# SparkFun_MicroMod_Function_Board_Blues_N.net
KiCad netlist of a schematic drawn in EAGLE
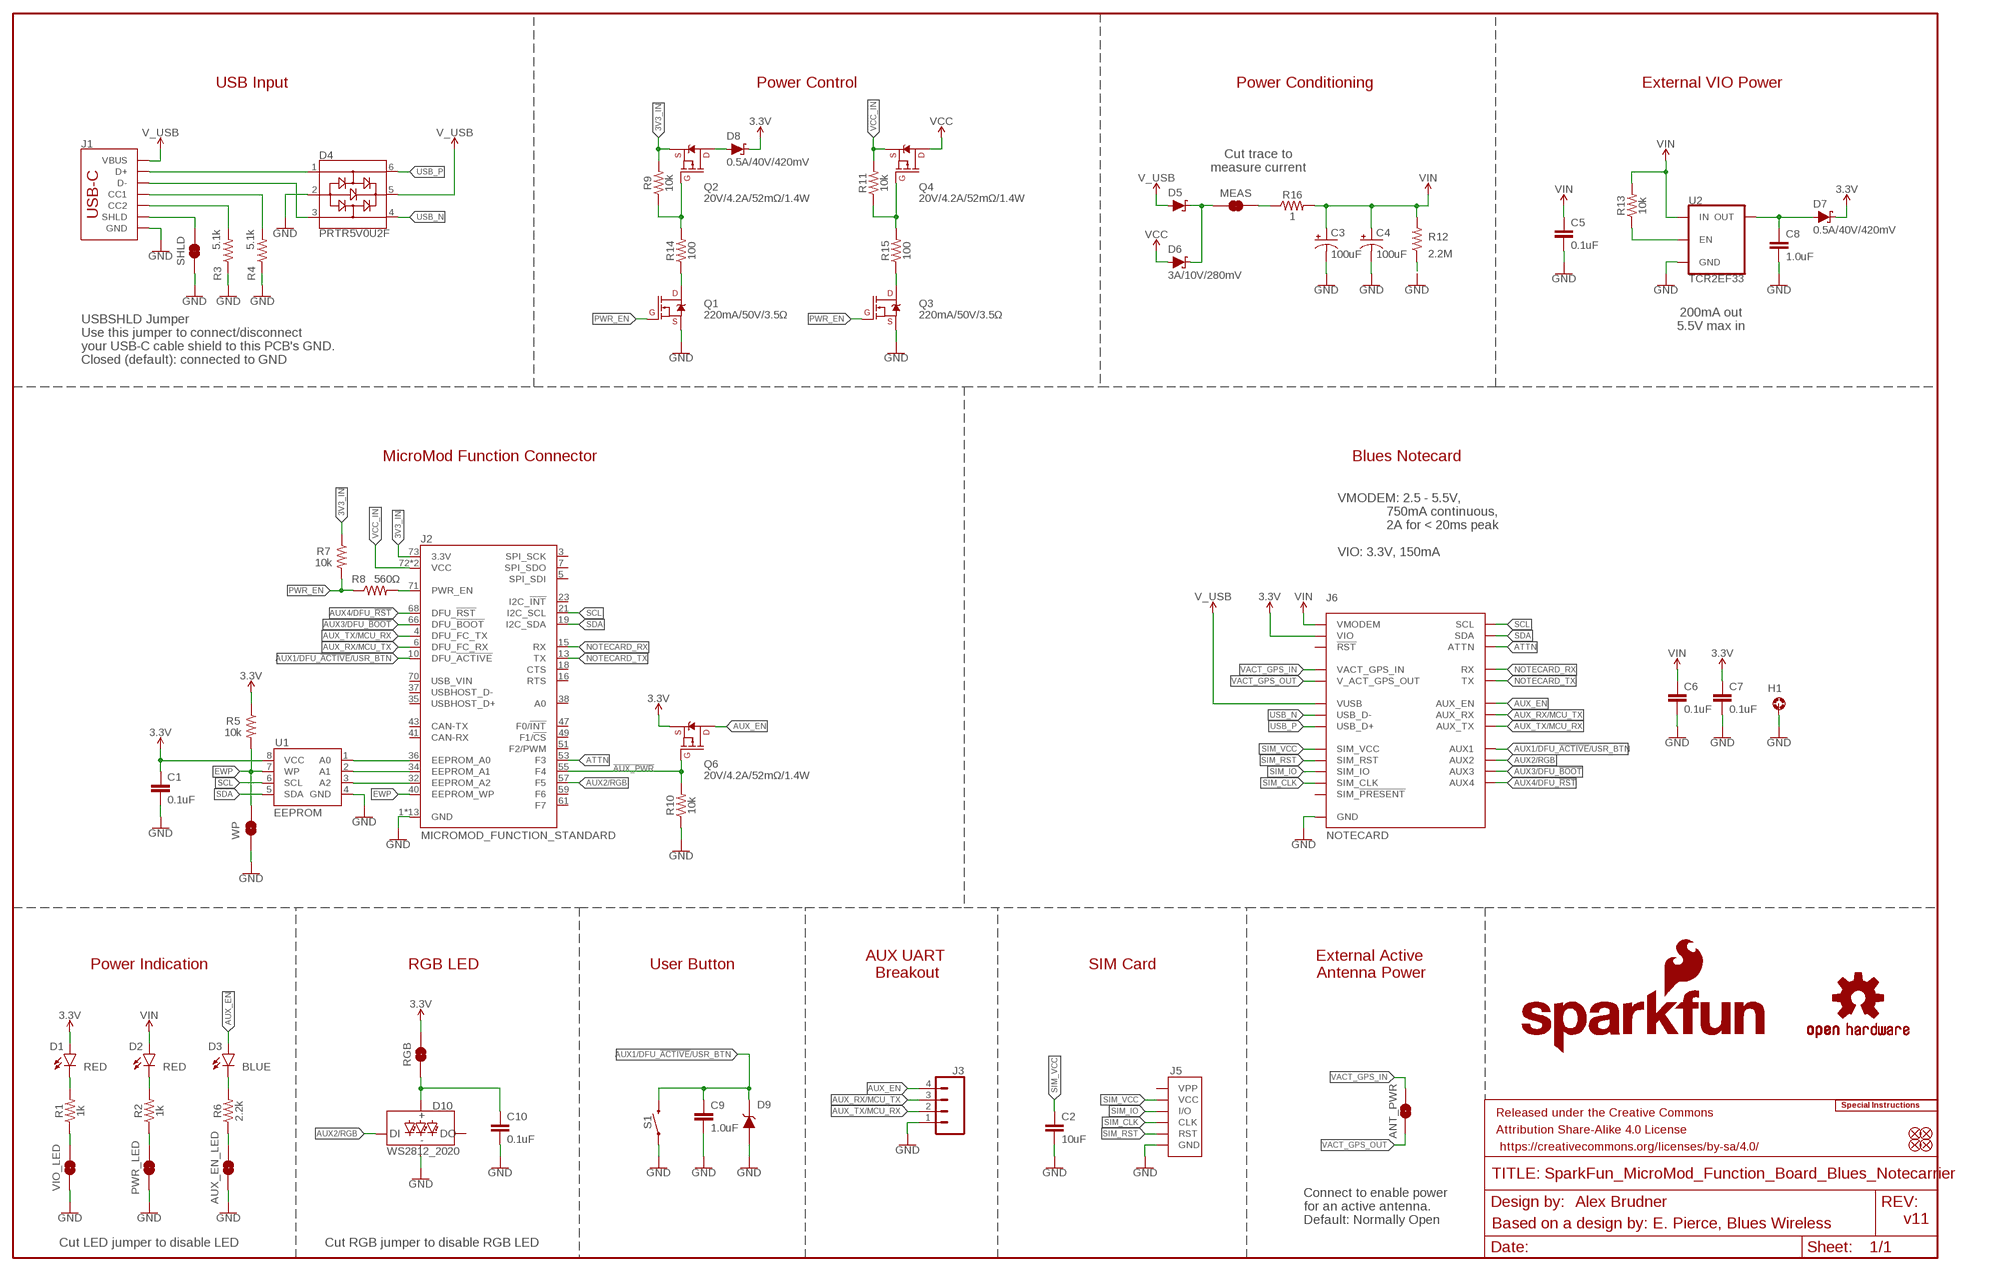
[diagram p0: schematic, sheet 1]

(export (version "E")
  (design (tool "Eeschema 10.0.6"))
  (components
    (comp (ref "ANT_PWR")
      (value "JUMPER-SMT_2_NO_SILK")
      (footprint "eagle-import:SMT-JUMPER_2_NO_SILK")
      (libsource (lib "eagle-import") (part "JUMPER-SMT_2_NO_SILK"))
    )
    (comp (ref "AUX_EN_LED")
      (value "JUMPER-SMT_2_NC_TRACE_SILK")
      (footprint "eagle-import:SMT-JUMPER_2_NC_TRACE_SILK")
      (libsource (lib "eagle-import") (part "JUMPER-SMT_2_NC_TRACE_SILK"))
    )
    (comp (ref "C1")
      (value "0.1uF")
      (footprint "eagle-import:0402-TIGHT")
      (libsource (lib "eagle-import") (part "0.1UF-0402T-16V-10%"))
    )
    (comp (ref "C2")
      (value "10uF")
      (footprint "eagle-import:0805")
      (libsource (lib "eagle-import") (part "10UF-0805-10V-10%"))
    )
    (comp (ref "C3")
      (value "100uF")
      (footprint "eagle-import:PANASONIC_D")
      (libsource (lib "eagle-import") (part "100UF-POLAR-25V-20%-SMD(ELEC)"))
    )
    (comp (ref "C4")
      (value "100uF")
      (footprint "eagle-import:PANASONIC_D")
      (libsource (lib "eagle-import") (part "100UF-POLAR-25V-20%-SMD(ELEC)"))
    )
    (comp (ref "C5")
      (value "0.1uF")
      (footprint "eagle-import:0402-TIGHT")
      (libsource (lib "eagle-import") (part "0.1UF-0402T-16V-10%"))
    )
    (comp (ref "C6")
      (value "0.1uF")
      (footprint "eagle-import:0402-TIGHT")
      (libsource (lib "eagle-import") (part "0.1UF-0402T-16V-10%"))
    )
    (comp (ref "C7")
      (value "0.1uF")
      (footprint "eagle-import:0402-TIGHT")
      (libsource (lib "eagle-import") (part "0.1UF-0402T-16V-10%"))
    )
    (comp (ref "C8")
      (value "1.0uF")
      (footprint "eagle-import:0402-TIGHT")
      (libsource (lib "eagle-import") (part "1.0UF-0402T-16V-10%"))
    )
    (comp (ref "C9")
      (value "1.0uF")
      (footprint "eagle-import:0402-TIGHT")
      (libsource (lib "eagle-import") (part "1.0UF-0402T-16V-10%"))
    )
    (comp (ref "C10")
      (value "0.1uF")
      (footprint "eagle-import:0402-TIGHT")
      (libsource (lib "eagle-import") (part "0.1UF-0402T-16V-10%"))
    )
    (comp (ref "D1")
      (value "RED")
      (footprint "eagle-import:LED-0603")
      (libsource (lib "eagle-import") (part "LED-RED0603"))
    )
    (comp (ref "D2")
      (value "RED")
      (footprint "eagle-import:LED-0603")
      (libsource (lib "eagle-import") (part "LED-RED0603"))
    )
    (comp (ref "D3")
      (value "BLUE")
      (footprint "eagle-import:LED-0603")
      (libsource (lib "eagle-import") (part "LED-BLUE0603"))
    )
    (comp (ref "D4")
      (value "PRTR5V0U2F")
      (footprint "eagle-import:SOT886")
      (libsource (lib "eagle-import") (part "PRTR5V0U2F"))
    )
    (comp (ref "D5")
      (value "3A/10V/280mV")
      (footprint "eagle-import:SOD-323")
      (libsource (lib "eagle-import") (part "DIODE-SCHOTTKY-BAT60A"))
    )
    (comp (ref "D6")
      (value "3A/10V/280mV")
      (footprint "eagle-import:SOD-323")
      (libsource (lib "eagle-import") (part "DIODE-SCHOTTKY-BAT60A"))
    )
    (comp (ref "D7")
      (value "0.5A/40V/420mV")
      (footprint "eagle-import:SOD-323")
      (libsource (lib "eagle-import") (part "DIODE-SCHOTTKY-PMEG4005EJ"))
    )
    (comp (ref "D8")
      (value "0.5A/40V/420mV")
      (footprint "eagle-import:SOD-323")
      (libsource (lib "eagle-import") (part "DIODE-SCHOTTKY-PMEG4005EJ"))
    )
    (comp (ref "D9")
      (value "SMBJP6KE-DNP")
      (footprint "eagle-import:DO-214AA")
      (libsource (lib "eagle-import") (part "SMBJP6KE-DNP"))
    )
    (comp (ref "D10")
      (value "WS2812_2020")
      (footprint "eagle-import:WS2812-2020")
      (libsource (lib "eagle-import") (part "WS2812_2020"))
    )
    (comp (ref "FD1")
      (value "FIDUCIALUFIDUCIAL")
      (footprint "eagle-import:FIDUCIAL-MICRO")
      (libsource (lib "eagle-import") (part "FIDUCIALUFIDUCIAL"))
    )
    (comp (ref "FD2")
      (value "FIDUCIALUFIDUCIAL")
      (footprint "eagle-import:FIDUCIAL-MICRO")
      (libsource (lib "eagle-import") (part "FIDUCIALUFIDUCIAL"))
    )
    (comp (ref "FD3")
      (value "FIDUCIALUFIDUCIAL")
      (footprint "eagle-import:FIDUCIAL-MICRO")
      (libsource (lib "eagle-import") (part "FIDUCIALUFIDUCIAL"))
    )
    (comp (ref "FD4")
      (value "FIDUCIALUFIDUCIAL")
      (footprint "eagle-import:FIDUCIAL-MICRO")
      (libsource (lib "eagle-import") (part "FIDUCIALUFIDUCIAL"))
    )
    (comp (ref "FRAME1")
      (value "FRAME-LEDGER")
      (footprint "eagle-import:CREATIVE_COMMONS")
      (libsource (lib "eagle-import") (part "FRAME-LEDGER"))
    )
    (comp (ref "H1")
      (value "STAND-OFF-REFLOW-M2.5_2.5MM_TALL")
      (footprint "eagle-import:STAND-OFF-REFLOW-M2.5")
      (libsource (lib "eagle-import") (part "STAND-OFF-REFLOW-M2.5_2.5MM_TALL"))
    )
    (comp (ref "J1")
      (value "USB_C_2-LAYER_PADS")
      (footprint "eagle-import:USB-C-16P-2LAYER-PADS")
      (libsource (lib "eagle-import") (part "USB_C_2-LAYER_PADS"))
    )
    (comp (ref "J2")
      (value "MICROMOD_FUNCTION_STANDARD")
      (footprint "eagle-import:M.2-CARD-E-22_FUNCTION_STANDARD")
      (libsource (lib "eagle-import") (part "MICROMOD_FUNCTION_STANDARD"))
    )
    (comp (ref "J3")
      (value "CONN_041X04_NO_SILK_NO_POP")
      (footprint "eagle-import:1X04_NO_SILK")
      (libsource (lib "eagle-import") (part "CONN_041X04_NO_SILK_NO_POP"))
    )
    (comp (ref "J5")
      (value "SIMHOLDER-NANOSIM-MOLEX")
      (footprint "eagle-import:NANO_SIM_MOLEX_104224-0820")
      (libsource (lib "eagle-import") (part "SIMHOLDER-NANOSIM-MOLEX"))
    )
    (comp (ref "J6")
      (value "NOTECARD")
      (footprint "eagle-import:M.2-CONNECTOR-E")
      (libsource (lib "eagle-import") (part "NOTECARD"))
    )
    (comp (ref "LOGO1")
      (value "SFE_LOGO_NAME_FLAME.1_INCH")
      (footprint "eagle-import:SFE_LOGO_NAME_FLAME_.1")
      (libsource (lib "eagle-import") (part "SFE_LOGO_NAME_FLAME.1_INCH"))
    )
    (comp (ref "LOGO2")
      (value "SPECIAL_INSTRUCTIONS-ORDERING")
      (footprint "eagle-import:ORDERING_INSTRUCTIONS")
      (libsource (lib "eagle-import") (part "SPECIAL_INSTRUCTIONS-ORDERING"))
    )
    (comp (ref "LOGO3")
      (value "OSHW-LOGOMINI")
      (footprint "eagle-import:OSHW-LOGO-MINI")
      (libsource (lib "eagle-import") (part "OSHW-LOGOMINI"))
    )
    (comp (ref "MEAS")
      (value "JUMPER-COMBO_2_NC_TRACE")
      (footprint "eagle-import:COMBO-JUMPER_2_NC_TRACE")
      (libsource (lib "eagle-import") (part "JUMPER-COMBO_2_NC_TRACE"))
    )
    (comp (ref "PWR_LED")
      (value "JUMPER-SMT_2_NC_TRACE_SILK")
      (footprint "eagle-import:SMT-JUMPER_2_NC_TRACE_SILK")
      (libsource (lib "eagle-import") (part "JUMPER-SMT_2_NC_TRACE_SILK"))
    )
    (comp (ref "Q1")
      (value "220mA/50V/3.5Ω")
      (footprint "eagle-import:SOT23-3")
      (libsource (lib "eagle-import") (part "MOSFET-NCH-BSS138"))
    )
    (comp (ref "Q2")
      (value "20V/4.2A/52mΩ/1.4W")
      (footprint "eagle-import:SOT23-3")
      (libsource (lib "eagle-import") (part "MOSFET_PCH-DMG2305UX-7"))
    )
    (comp (ref "Q3")
      (value "220mA/50V/3.5Ω")
      (footprint "eagle-import:SOT23-3")
      (libsource (lib "eagle-import") (part "MOSFET-NCH-BSS138"))
    )
    (comp (ref "Q4")
      (value "20V/4.2A/52mΩ/1.4W")
      (footprint "eagle-import:SOT23-3")
      (libsource (lib "eagle-import") (part "MOSFET_PCH-DMG2305UX-7"))
    )
    (comp (ref "Q6")
      (value "20V/4.2A/52mΩ/1.4W")
      (footprint "eagle-import:SOT23-3")
      (libsource (lib "eagle-import") (part "MOSFET_PCH-DMG2305UX-7"))
    )
    (comp (ref "R1")
      (value "1k")
      (footprint "eagle-import:0402-TIGHT")
      (libsource (lib "eagle-import") (part "1KOHM-0402T-1/16W-1%"))
    )
    (comp (ref "R2")
      (value "1k")
      (footprint "eagle-import:0402-TIGHT")
      (libsource (lib "eagle-import") (part "1KOHM-0402T-1/16W-1%"))
    )
    (comp (ref "R3")
      (value "5.1k")
      (footprint "eagle-import:0402-TIGHT")
      (libsource (lib "eagle-import") (part "5.1KOHM-0402T-1/16W-1%"))
    )
    (comp (ref "R4")
      (value "5.1k")
      (footprint "eagle-import:0402-TIGHT")
      (libsource (lib "eagle-import") (part "5.1KOHM-0402T-1/16W-1%"))
    )
    (comp (ref "R5")
      (value "10k")
      (footprint "eagle-import:0402-TIGHT")
      (libsource (lib "eagle-import") (part "10KOHM-0402T-1/16W-1%"))
    )
    (comp (ref "R6")
      (value "2.2k")
      (footprint "eagle-import:0402-TIGHT")
      (libsource (lib "eagle-import") (part "2.2KOHM-0402T-1/16W-1%"))
    )
    (comp (ref "R7")
      (value "10k")
      (footprint "eagle-import:0402-TIGHT")
      (libsource (lib "eagle-import") (part "10KOHM-0402T-1/16W-1%"))
    )
    (comp (ref "R8")
      (value "560Ω")
      (footprint "eagle-import:0402-TIGHT")
      (libsource (lib "eagle-import") (part "560OHM_0402_TIGHT"))
    )
    (comp (ref "R9")
      (value "10k")
      (footprint "eagle-import:0402-TIGHT")
      (libsource (lib "eagle-import") (part "10KOHM-0402T-1/16W-1%"))
    )
    (comp (ref "R10")
      (value "10k")
      (footprint "eagle-import:0402-TIGHT")
      (libsource (lib "eagle-import") (part "10KOHM-0402T-1/16W-1%"))
    )
    (comp (ref "R11")
      (value "10k")
      (footprint "eagle-import:0402-TIGHT")
      (libsource (lib "eagle-import") (part "10KOHM-0402T-1/16W-1%"))
    )
    (comp (ref "R12")
      (value "2.2M")
      (footprint "eagle-import:0402-TIGHT")
      (libsource (lib "eagle-import") (part "2.2MOHMS-0402T-1/10W-1%"))
    )
    (comp (ref "R13")
      (value "10k")
      (footprint "eagle-import:0402-TIGHT")
      (libsource (lib "eagle-import") (part "10KOHM-0402T-1/16W-1%"))
    )
    (comp (ref "R14")
      (value "100")
      (footprint "eagle-import:0402-TIGHT")
      (libsource (lib "eagle-import") (part "100OHM-0402-TIGHT-1/16W-1%"))
    )
    (comp (ref "R15")
      (value "100")
      (footprint "eagle-import:0402-TIGHT")
      (libsource (lib "eagle-import") (part "100OHM-0402-TIGHT-1/16W-1%"))
    )
    (comp (ref "R16")
      (value "1")
      (footprint "eagle-import:0603")
      (libsource (lib "eagle-import") (part "1OHM-0603-1/10W-1%"))
    )
    (comp (ref "RGB")
      (value "JUMPER-SMT_2_NC_TRACE_SILK")
      (footprint "eagle-import:SMT-JUMPER_2_NC_TRACE_SILK")
      (libsource (lib "eagle-import") (part "JUMPER-SMT_2_NC_TRACE_SILK"))
    )
    (comp (ref "S1")
      (value "MOMENTARY-SWITCH-SPST-SMD-4.6X2.8MM")
      (footprint "eagle-import:TACTILE_SWITCH_SMD_4.6X2.8MM")
      (libsource (lib "eagle-import") (part "MOMENTARY-SWITCH-SPST-SMD-4.6X2.8MM"))
    )
    (comp (ref "SHLD")
      (value "JUMPER-SMT_2_NC_TRACE_SILK")
      (footprint "eagle-import:SMT-JUMPER_2_NC_TRACE_SILK")
      (libsource (lib "eagle-import") (part "JUMPER-SMT_2_NC_TRACE_SILK"))
    )
    (comp (ref "U1")
      (value "EEPROM")
      (footprint "eagle-import:SO08")
      (libsource (lib "eagle-import") (part "EEPROM-I2C512K"))
    )
    (comp (ref "U2")
      (value "TCR2EF33")
      (footprint "eagle-import:SOT23-5")
      (libsource (lib "eagle-import") (part "TCR2EF33"))
    )
    (comp (ref "VIO_LED")
      (value "JUMPER-SMT_2_NC_TRACE_SILK")
      (footprint "eagle-import:SMT-JUMPER_2_NC_TRACE_SILK")
      (libsource (lib "eagle-import") (part "JUMPER-SMT_2_NC_TRACE_SILK"))
    )
    (comp (ref "WP")
      (value "JUMPER-SMT_2_NO_SILK")
      (footprint "eagle-import:SMT-JUMPER_2_NO_SILK")
      (libsource (lib "eagle-import") (part "JUMPER-SMT_2_NO_SILK"))
    )
  )
  (nets
    (net (code "1") (name "/AUX1{slash}DFU_~{ACTIVE}{slash}USR_BTN") (class "Default")
      (node (ref "C9") (pin "1") (pinfunction "1_1") (pintype "passive"))
      (node (ref "D9") (pin "C") (pinfunction "C_C") (pintype "passive"))
      (node (ref "J2") (pin "10") (pinfunction "DFU_~{ACTIVE}_10") (pintype "bidirectional"))
      (node (ref "J6") (pin "46") (pinfunction "AUX1_46") (pintype "bidirectional"))
      (node (ref "S1") (pin "3") (pinfunction "2_3") (pintype "passive"))
      (node (ref "S1") (pin "4") (pinfunction "2_4") (pintype "passive"))
    )
    (net (code "2") (name "/AUX3{slash}DFU_~{BOOT}") (class "Default")
      (node (ref "J2") (pin "66") (pinfunction "DFU_~{BOOT}_66") (pintype "bidirectional"))
      (node (ref "J6") (pin "50") (pinfunction "AUX3_50") (pintype "bidirectional"))
    )
    (net (code "3") (name "/AUX4{slash}DFU_~{RST}") (class "Default")
      (node (ref "J2") (pin "68") (pinfunction "DFU_~{RST}_68") (pintype "bidirectional"))
      (node (ref "J6") (pin "52") (pinfunction "AUX4_52") (pintype "bidirectional"))
    )
    (net (code "4") (name "/~{AUX_PWR}") (class "Default")
      (node (ref "J2") (pin "55") (pinfunction "F4_55") (pintype "bidirectional"))
      (node (ref "Q6") (pin "1") (pinfunction "G_1") (pintype "bidirectional"))
      (node (ref "R10") (pin "2") (pinfunction "2_2") (pintype "passive"))
    )
    (net (code "5") (name "3.3V") (class "Default")
      (node (ref "C1") (pin "1") (pinfunction "1_1") (pintype "passive"))
      (node (ref "C7") (pin "1") (pinfunction "1_1") (pintype "passive"))
      (node (ref "D1") (pin "A") (pinfunction "A_A") (pintype "passive"))
      (node (ref "D7") (pin "C") (pinfunction "C_C") (pintype "passive"))
      (node (ref "D8") (pin "C") (pinfunction "C_C") (pintype "passive"))
      (node (ref "J6") (pin "2") (pinfunction "VIO_2") (pintype "bidirectional"))
      (node (ref "J6") (pin "4") (pinfunction "VIO_4") (pintype "bidirectional"))
      (node (ref "Q6") (pin "2") (pinfunction "S_2") (pintype "bidirectional"))
      (node (ref "R5") (pin "1") (pinfunction "1_1") (pintype "passive"))
      (node (ref "RGB") (pin "2") (pinfunction "2_2") (pintype "passive"))
      (node (ref "U1") (pin "8") (pinfunction "VCC_8") (pintype "power_in"))
    )
    (net (code "6") (name "3V3_IN") (class "Default")
      (node (ref "J2") (pin "73") (pinfunction "3.3V_73") (pintype "bidirectional"))
      (node (ref "Q2") (pin "2") (pinfunction "S_2") (pintype "bidirectional"))
      (node (ref "R7") (pin "1") (pinfunction "1_1") (pintype "passive"))
      (node (ref "R9") (pin "2") (pinfunction "2_2") (pintype "passive"))
    )
    (net (code "7") (name "ATTN") (class "Default")
      (node (ref "J2") (pin "53") (pinfunction "F3_53") (pintype "bidirectional"))
      (node (ref "J6") (pin "54") (pinfunction "ATTN_54") (pintype "bidirectional"))
    )
    (net (code "8") (name "AUX2{slash}RGB") (class "Default")
      (node (ref "D10") (pin "DI") (pinfunction "DI_DI") (pintype "bidirectional"))
      (node (ref "J2") (pin "57") (pinfunction "F5_57") (pintype "bidirectional"))
      (node (ref "J6") (pin "48") (pinfunction "AUX2_48") (pintype "bidirectional"))
    )
    (net (code "9") (name "AUX_EN") (class "Default")
      (node (ref "D3") (pin "A") (pinfunction "A_A") (pintype "passive"))
      (node (ref "J3") (pin "4") (pinfunction "4_4") (pintype "passive"))
      (node (ref "J6") (pin "56") (pinfunction "AUX_EN_56") (pintype "bidirectional"))
      (node (ref "Q6") (pin "3") (pinfunction "D_3") (pintype "bidirectional"))
    )
    (net (code "10") (name "AUX_RX{slash}MCU_TX") (class "Default")
      (node (ref "J2") (pin "6") (pinfunction "DFU_FC_RX_6") (pintype "bidirectional"))
      (node (ref "J3") (pin "3") (pinfunction "3_3") (pintype "passive"))
      (node (ref "J6") (pin "58") (pinfunction "AUX_RX_58") (pintype "bidirectional"))
    )
    (net (code "11") (name "AUX_TX{slash}MCU_RX") (class "Default")
      (node (ref "J2") (pin "4") (pinfunction "DFU_FC_TX_4") (pintype "bidirectional"))
      (node (ref "J3") (pin "2") (pinfunction "2_2") (pintype "passive"))
      (node (ref "J6") (pin "60") (pinfunction "AUX_TX_60") (pintype "bidirectional"))
    )
    (net (code "12") (name "EWP") (class "Default")
      (node (ref "J2") (pin "40") (pinfunction "EEPROM_WP_40") (pintype "bidirectional"))
      (node (ref "R5") (pin "2") (pinfunction "2_2") (pintype "passive"))
      (node (ref "U1") (pin "7") (pinfunction "WP_7") (pintype "bidirectional"))
      (node (ref "WP") (pin "2") (pinfunction "2_2") (pintype "passive"))
    )
    (net (code "13") (name "GND") (class "Default")
      (node (ref "AUX_EN_LED") (pin "1") (pinfunction "1_1") (pintype "passive"))
      (node (ref "C1") (pin "2") (pinfunction "2_2") (pintype "passive"))
      (node (ref "C10") (pin "2") (pinfunction "2_2") (pintype "passive"))
      (node (ref "C2") (pin "2") (pinfunction "2_2") (pintype "passive"))
      (node (ref "C3") (pin "-") (pinfunction "-_-") (pintype "passive"))
      (node (ref "C4") (pin "-") (pinfunction "-_-") (pintype "passive"))
      (node (ref "C5") (pin "2") (pinfunction "2_2") (pintype "passive"))
      (node (ref "C6") (pin "2") (pinfunction "2_2") (pintype "passive"))
      (node (ref "C7") (pin "2") (pinfunction "2_2") (pintype "passive"))
      (node (ref "C8") (pin "2") (pinfunction "2_2") (pintype "passive"))
      (node (ref "C9") (pin "2") (pinfunction "2_2") (pintype "passive"))
      (node (ref "D10") (pin "GND") (pinfunction "GND_GND") (pintype "bidirectional"))
      (node (ref "D4") (pin "2") (pinfunction "2_2") (pintype "power_in"))
      (node (ref "D9") (pin "A") (pinfunction "A_A") (pintype "passive"))
      (node (ref "H1") (pin "1") (pinfunction "1_1") (pintype "bidirectional"))
      (node (ref "J1") (pin "GND") (pinfunction "GND_GND") (pintype "bidirectional"))
      (node (ref "J1") (pin "GND2") (pinfunction "GND_GND2") (pintype "bidirectional"))
      (node (ref "J2") (pin "1") (pinfunction "GND_1") (pintype "bidirectional"))
      (node (ref "J2") (pin "2") (pinfunction "GND_2") (pintype "bidirectional"))
      (node (ref "J2") (pin "33") (pinfunction "GND_33") (pintype "bidirectional"))
      (node (ref "J2") (pin "39") (pinfunction "GND_39") (pintype "bidirectional"))
      (node (ref "J2") (pin "45") (pinfunction "GND_45") (pintype "bidirectional"))
      (node (ref "J2") (pin "75") (pinfunction "GND_75") (pintype "bidirectional"))
      (node (ref "J2") (pin "8") (pinfunction "GND_8") (pintype "bidirectional"))
      (node (ref "J2") (pin "GND1") (pinfunction "GND_GND1") (pintype "bidirectional"))
      (node (ref "J2") (pin "GND2") (pinfunction "GND_GND2") (pintype "bidirectional"))
      (node (ref "J2") (pin "GND3") (pinfunction "GND_GND3") (pintype "bidirectional"))
      (node (ref "J2") (pin "GND4") (pinfunction "GND_GND4") (pintype "bidirectional"))
      (node (ref "J2") (pin "GND5") (pinfunction "GND_GND5") (pintype "bidirectional"))
      (node (ref "J2") (pin "GND6") (pinfunction "GND_GND6") (pintype "bidirectional"))
      (node (ref "J3") (pin "1") (pinfunction "1_1") (pintype "passive"))
      (node (ref "J5") (pin "G1") (pinfunction "GND_G1") (pintype "power_in"))
      (node (ref "J5") (pin "G2") (pinfunction "GND_G2") (pintype "power_in"))
      (node (ref "J5") (pin "G3") (pinfunction "GND_G3") (pintype "power_in"))
      (node (ref "J5") (pin "G4") (pinfunction "GND_G4") (pintype "power_in"))
      (node (ref "J5") (pin "S4") (pinfunction "GND_S4") (pintype "power_in"))
      (node (ref "J6") (pin "11") (pinfunction "GND_11") (pintype "bidirectional"))
      (node (ref "J6") (pin "18") (pinfunction "GND_18") (pintype "bidirectional"))
      (node (ref "J6") (pin "3") (pinfunction "GND_3") (pintype "bidirectional"))
      (node (ref "J6") (pin "33") (pinfunction "GND_33") (pintype "bidirectional"))
      (node (ref "J6") (pin "39") (pinfunction "GND_39") (pintype "bidirectional"))
      (node (ref "J6") (pin "45") (pinfunction "GND_45") (pintype "bidirectional"))
      (node (ref "J6") (pin "5") (pinfunction "GND_5") (pintype "bidirectional"))
      (node (ref "J6") (pin "51") (pinfunction "GND_51") (pintype "bidirectional"))
      (node (ref "J6") (pin "57") (pinfunction "GND_57") (pintype "bidirectional"))
      (node (ref "J6") (pin "6") (pinfunction "GND_6") (pintype "bidirectional"))
      (node (ref "J6") (pin "71") (pinfunction "GND_71") (pintype "bidirectional"))
      (node (ref "J6") (pin "73") (pinfunction "GND_73") (pintype "bidirectional"))
      (node (ref "PWR_LED") (pin "1") (pinfunction "1_1") (pintype "passive"))
      (node (ref "Q1") (pin "2") (pinfunction "S_2") (pintype "bidirectional"))
      (node (ref "Q3") (pin "2") (pinfunction "S_2") (pintype "bidirectional"))
      (node (ref "R10") (pin "1") (pinfunction "1_1") (pintype "passive"))
      (node (ref "R12") (pin "1") (pinfunction "1_1") (pintype "passive"))
      (node (ref "R3") (pin "1") (pinfunction "1_1") (pintype "passive"))
      (node (ref "R4") (pin "1") (pinfunction "1_1") (pintype "passive"))
      (node (ref "S1") (pin "1") (pinfunction "1_1") (pintype "passive"))
      (node (ref "S1") (pin "2") (pinfunction "1_2") (pintype "passive"))
      (node (ref "SHLD") (pin "1") (pinfunction "1_1") (pintype "passive"))
      (node (ref "U1") (pin "4") (pinfunction "GND_4") (pintype "power_in"))
      (node (ref "U2") (pin "2") (pinfunction "GND_2") (pintype "input"))
      (node (ref "VIO_LED") (pin "1") (pinfunction "1_1") (pintype "passive"))
      (node (ref "WP") (pin "1") (pinfunction "1_1") (pintype "passive"))
    )
    (net (code "14") (name "NOTECARD_RX") (class "Default")
      (node (ref "J2") (pin "15") (pinfunction "RX_15") (pintype "bidirectional"))
      (node (ref "J6") (pin "62") (pinfunction "RX_62") (pintype "bidirectional"))
    )
    (net (code "15") (name "NOTECARD_TX") (class "Default")
      (node (ref "J2") (pin "13") (pinfunction "TX_13") (pintype "bidirectional"))
      (node (ref "J6") (pin "64") (pinfunction "TX_64") (pintype "bidirectional"))
    )
    (net (code "16") (name "Net-(AUX_EN_LED-Pad2)") (class "Default")
      (node (ref "AUX_EN_LED") (pin "2") (pinfunction "2_2") (pintype "passive"))
      (node (ref "R6") (pin "1") (pinfunction "1_1") (pintype "passive"))
    )
    (net (code "17") (name "Net-(C10-Pad1)") (class "Default")
      (node (ref "C10") (pin "1") (pinfunction "1_1") (pintype "passive"))
      (node (ref "D10") (pin "VCC") (pinfunction "VCC_VCC") (pintype "bidirectional"))
      (node (ref "RGB") (pin "1") (pinfunction "1_1") (pintype "passive"))
    )
    (net (code "18") (name "Net-(D1-PadC)") (class "Default")
      (node (ref "D1") (pin "C") (pinfunction "C_C") (pintype "passive"))
      (node (ref "R1") (pin "2") (pinfunction "2_2") (pintype "passive"))
    )
    (net (code "19") (name "Net-(D2-PadC)") (class "Default")
      (node (ref "D2") (pin "C") (pinfunction "C_C") (pintype "passive"))
      (node (ref "R2") (pin "2") (pinfunction "2_2") (pintype "passive"))
    )
    (net (code "20") (name "Net-(D3-PadC)") (class "Default")
      (node (ref "D3") (pin "C") (pinfunction "C_C") (pintype "passive"))
      (node (ref "R6") (pin "2") (pinfunction "2_2") (pintype "passive"))
    )
    (net (code "21") (name "Net-(D4-Pad1)") (class "Default")
      (node (ref "D4") (pin "1") (pinfunction "1_1") (pintype "bidirectional"))
      (node (ref "J1") (pin "A6") (pinfunction "D+_A6") (pintype "bidirectional"))
      (node (ref "J1") (pin "B6") (pinfunction "D+_B6") (pintype "bidirectional"))
    )
    (net (code "22") (name "Net-(D4-Pad3)") (class "Default")
      (node (ref "D4") (pin "3") (pinfunction "3_3") (pintype "bidirectional"))
      (node (ref "J1") (pin "A7") (pinfunction "D-_A7") (pintype "bidirectional"))
      (node (ref "J1") (pin "B7") (pinfunction "D-_B7") (pintype "bidirectional"))
    )
    (net (code "23") (name "Net-(D5-PadC)") (class "Default")
      (node (ref "D5") (pin "C") (pinfunction "C_C") (pintype "passive"))
      (node (ref "D6") (pin "C") (pinfunction "C_C") (pintype "passive"))
      (node (ref "MEAS") (pin "1") (pinfunction "1_1") (pintype "passive"))
      (node (ref "MEAS") (pin "3") (pinfunction "1_3") (pintype "passive"))
    )
    (net (code "24") (name "Net-(J1-CC1)") (class "Default")
      (node (ref "J1") (pin "A5") (pinfunction "CC1_A5") (pintype "bidirectional"))
      (node (ref "R4") (pin "2") (pinfunction "2_2") (pintype "passive"))
    )
    (net (code "25") (name "Net-(J1-CC2)") (class "Default")
      (node (ref "J1") (pin "B5") (pinfunction "CC2_B5") (pintype "bidirectional"))
      (node (ref "R3") (pin "2") (pinfunction "2_2") (pintype "passive"))
    )
    (net (code "26") (name "Net-(J1-SHLD-PadSHLD1)") (class "Default")
      (node (ref "J1") (pin "SHLD1") (pinfunction "SHLD_SHLD1") (pintype "bidirectional"))
      (node (ref "J1") (pin "SHLD2") (pinfunction "SHLD_SHLD2") (pintype "bidirectional"))
      (node (ref "J1") (pin "SHLD3") (pinfunction "SHLD_SHLD3") (pintype "bidirectional"))
      (node (ref "J1") (pin "SHLD4") (pinfunction "SHLD_SHLD4") (pintype "bidirectional"))
      (node (ref "SHLD") (pin "2") (pinfunction "2_2") (pintype "passive"))
    )
    (net (code "27") (name "Net-(J2-EEPROM_A0)") (class "Default")
      (node (ref "J2") (pin "36") (pinfunction "EEPROM_A0_36") (pintype "bidirectional"))
      (node (ref "U1") (pin "1") (pinfunction "A0_1") (pintype "bidirectional"))
    )
    (net (code "28") (name "Net-(J2-EEPROM_A1)") (class "Default")
      (node (ref "J2") (pin "34") (pinfunction "EEPROM_A1_34") (pintype "bidirectional"))
      (node (ref "U1") (pin "2") (pinfunction "A1_2") (pintype "bidirectional"))
    )
    (net (code "29") (name "Net-(J2-EEPROM_A2)") (class "Default")
      (node (ref "J2") (pin "32") (pinfunction "EEPROM_A2_32") (pintype "bidirectional"))
      (node (ref "U1") (pin "3") (pinfunction "A2_3") (pintype "bidirectional"))
    )
    (net (code "30") (name "Net-(J2-PWR_EN)") (class "Default")
      (node (ref "J2") (pin "71") (pinfunction "PWR_EN_71") (pintype "bidirectional"))
      (node (ref "R8") (pin "2") (pinfunction "2_2") (pintype "passive"))
    )
    (net (code "31") (name "Net-(MEAS-2-Pad4)") (class "Default")
      (node (ref "MEAS") (pin "2") (pinfunction "2_2") (pintype "passive"))
      (node (ref "MEAS") (pin "4") (pinfunction "2_4") (pintype "passive"))
      (node (ref "R16") (pin "1") (pinfunction "1_1") (pintype "passive"))
    )
    (net (code "32") (name "Net-(PWR_LED-Pad2)") (class "Default")
      (node (ref "PWR_LED") (pin "2") (pinfunction "2_2") (pintype "passive"))
      (node (ref "R2") (pin "1") (pinfunction "1_1") (pintype "passive"))
    )
    (net (code "33") (name "Net-(Q1-D)") (class "Default")
      (node (ref "Q1") (pin "3") (pinfunction "D_3") (pintype "bidirectional"))
      (node (ref "R14") (pin "1") (pinfunction "1_1") (pintype "passive"))
    )
    (net (code "34") (name "Net-(Q2-D)") (class "Default")
      (node (ref "D8") (pin "A") (pinfunction "A_A") (pintype "passive"))
      (node (ref "Q2") (pin "3") (pinfunction "D_3") (pintype "bidirectional"))
    )
    (net (code "35") (name "Net-(Q2-G)") (class "Default")
      (node (ref "Q2") (pin "1") (pinfunction "G_1") (pintype "bidirectional"))
      (node (ref "R14") (pin "2") (pinfunction "2_2") (pintype "passive"))
      (node (ref "R9") (pin "1") (pinfunction "1_1") (pintype "passive"))
    )
    (net (code "36") (name "Net-(Q3-D)") (class "Default")
      (node (ref "Q3") (pin "3") (pinfunction "D_3") (pintype "bidirectional"))
      (node (ref "R15") (pin "1") (pinfunction "1_1") (pintype "passive"))
    )
    (net (code "37") (name "Net-(Q4-G)") (class "Default")
      (node (ref "Q4") (pin "1") (pinfunction "G_1") (pintype "bidirectional"))
      (node (ref "R11") (pin "1") (pinfunction "1_1") (pintype "passive"))
      (node (ref "R15") (pin "2") (pinfunction "2_2") (pintype "passive"))
    )
    (net (code "38") (name "Net-(R1-Pad1)") (class "Default")
      (node (ref "R1") (pin "1") (pinfunction "1_1") (pintype "passive"))
      (node (ref "VIO_LED") (pin "2") (pinfunction "2_2") (pintype "passive"))
    )
    (net (code "39") (name "Net-(U2-EN)") (class "Default")
      (node (ref "R13") (pin "1") (pinfunction "1_1") (pintype "passive"))
      (node (ref "U2") (pin "3") (pinfunction "EN_3") (pintype "input"))
    )
    (net (code "40") (name "Net-(U2-OUT)") (class "Default")
      (node (ref "C8") (pin "1") (pinfunction "1_1") (pintype "passive"))
      (node (ref "D7") (pin "A") (pinfunction "A_A") (pintype "passive"))
      (node (ref "U2") (pin "5") (pinfunction "OUT_5") (pintype "passive"))
    )
    (net (code "41") (name "PWR_EN") (class "Default")
      (node (ref "Q1") (pin "1") (pinfunction "G_1") (pintype "bidirectional"))
      (node (ref "Q3") (pin "1") (pinfunction "G_1") (pintype "bidirectional"))
      (node (ref "R7") (pin "2") (pinfunction "2_2") (pintype "passive"))
      (node (ref "R8") (pin "1") (pinfunction "1_1") (pintype "passive"))
    )
    (net (code "42") (name "SCL") (class "Default")
      (node (ref "J2") (pin "21") (pinfunction "I2C_SCL_21") (pintype "bidirectional"))
      (node (ref "J6") (pin "40") (pinfunction "SCL_40") (pintype "bidirectional"))
      (node (ref "U1") (pin "6") (pinfunction "SCL_6") (pintype "bidirectional"))
    )
    (net (code "43") (name "SDA") (class "Default")
      (node (ref "J2") (pin "19") (pinfunction "I2C_SDA_19") (pintype "bidirectional"))
      (node (ref "J6") (pin "42") (pinfunction "SDA_42") (pintype "bidirectional"))
      (node (ref "U1") (pin "5") (pinfunction "SDA_5") (pintype "bidirectional"))
    )
    (net (code "44") (name "SIM_CLK") (class "Default")
      (node (ref "J5") (pin "S3") (pinfunction "CLK_S3") (pintype "input"))
      (node (ref "J6") (pin "14") (pinfunction "SIM_CLK_14") (pintype "bidirectional"))
    )
    (net (code "45") (name "SIM_IO") (class "Default")
      (node (ref "J5") (pin "S6") (pinfunction "I/O_S6") (pintype "bidirectional"))
      (node (ref "J6") (pin "12") (pinfunction "SIM_IO_12") (pintype "bidirectional"))
    )
    (net (code "46") (name "SIM_RST") (class "Default")
      (node (ref "J5") (pin "S2") (pinfunction "RST_S2") (pintype "input"))
      (node (ref "J6") (pin "10") (pinfunction "SIM_RST_10") (pintype "bidirectional"))
    )
    (net (code "47") (name "SIM_VCC") (class "Default")
      (node (ref "C2") (pin "1") (pinfunction "1_1") (pintype "passive"))
      (node (ref "J5") (pin "S1") (pinfunction "VCC_S1") (pintype "power_in"))
      (node (ref "J6") (pin "8") (pinfunction "SIM_VCC_8") (pintype "bidirectional"))
    )
    (net (code "48") (name "USB_N") (class "Default")
      (node (ref "D4") (pin "4") (pinfunction "4_4") (pintype "bidirectional"))
      (node (ref "J6") (pin "9") (pinfunction "USB_D-_9") (pintype "bidirectional"))
    )
    (net (code "49") (name "USB_P") (class "Default")
      (node (ref "D4") (pin "6") (pinfunction "6_6") (pintype "bidirectional"))
      (node (ref "J6") (pin "7") (pinfunction "USB_D+_7") (pintype "bidirectional"))
    )
    (net (code "50") (name "VACT_GPS_IN") (class "Default")
      (node (ref "ANT_PWR") (pin "2") (pinfunction "2_2") (pintype "passive"))
      (node (ref "J6") (pin "22") (pinfunction "VACT_GPS_IN_22") (pintype "bidirectional"))
    )
    (net (code "51") (name "VACT_GPS_OUT") (class "Default")
      (node (ref "ANT_PWR") (pin "1") (pinfunction "1_1") (pintype "passive"))
      (node (ref "J6") (pin "20") (pinfunction "V_ACT_GPS_OUT_20") (pintype "bidirectional"))
    )
    (net (code "52") (name "VCC") (class "Default")
      (node (ref "D6") (pin "A") (pinfunction "A_A") (pintype "passive"))
      (node (ref "Q4") (pin "3") (pinfunction "D_3") (pintype "bidirectional"))
    )
    (net (code "53") (name "VCC_IN") (class "Default")
      (node (ref "J2") (pin "72") (pinfunction "VCC_72") (pintype "bidirectional"))
      (node (ref "J2") (pin "74") (pinfunction "VCC_74") (pintype "bidirectional"))
      (node (ref "Q4") (pin "2") (pinfunction "S_2") (pintype "bidirectional"))
      (node (ref "R11") (pin "2") (pinfunction "2_2") (pintype "passive"))
    )
    (net (code "54") (name "VIN") (class "Default")
      (node (ref "C3") (pin "+") (pinfunction "+_+") (pintype "passive"))
      (node (ref "C4") (pin "+") (pinfunction "+_+") (pintype "passive"))
      (node (ref "C5") (pin "1") (pinfunction "1_1") (pintype "passive"))
      (node (ref "C6") (pin "1") (pinfunction "1_1") (pintype "passive"))
      (node (ref "D2") (pin "A") (pinfunction "A_A") (pintype "passive"))
      (node (ref "J6") (pin "70") (pinfunction "VMODEM_70") (pintype "bidirectional"))
      (node (ref "J6") (pin "72") (pinfunction "VMODEM_72") (pintype "bidirectional"))
      (node (ref "J6") (pin "74") (pinfunction "VMODEM_74") (pintype "bidirectional"))
      (node (ref "R12") (pin "2") (pinfunction "2_2") (pintype "passive"))
      (node (ref "R13") (pin "2") (pinfunction "2_2") (pintype "passive"))
      (node (ref "R16") (pin "2") (pinfunction "2_2") (pintype "passive"))
      (node (ref "U2") (pin "1") (pinfunction "IN_1") (pintype "input"))
    )
    (net (code "55") (name "V_USB") (class "Default")
      (node (ref "D4") (pin "5") (pinfunction "5_5") (pintype "power_in"))
      (node (ref "D5") (pin "A") (pinfunction "A_A") (pintype "passive"))
      (node (ref "J1") (pin "VBUS1") (pinfunction "VBUS_VBUS1") (pintype "bidirectional"))
      (node (ref "J1") (pin "VBUS2") (pinfunction "VBUS_VBUS2") (pintype "bidirectional"))
      (node (ref "J6") (pin "13") (pinfunction "VUSB_13") (pintype "bidirectional"))
    )
    (net (code "56") (name "unconnected-(D10-PadDO)") (class "Default")
      (node (ref "D10") (pin "DO") (pinfunction "DO_DO") (pintype "bidirectional"))
    )
    (net (code "57") (name "unconnected-(J2-A0-Pad38)") (class "Default")
      (node (ref "J2") (pin "38") (pinfunction "A0_38") (pintype "bidirectional"))
    )
    (net (code "58") (name "unconnected-(J2-CAN-RX-Pad41)") (class "Default")
      (node (ref "J2") (pin "41") (pinfunction "CAN-RX_41") (pintype "bidirectional"))
    )
    (net (code "59") (name "unconnected-(J2-CAN-TX-Pad43)") (class "Default")
      (node (ref "J2") (pin "43") (pinfunction "CAN-TX_43") (pintype "bidirectional"))
    )
    (net (code "60") (name "unconnected-(J2-CTS-Pad18)") (class "Default")
      (node (ref "J2") (pin "18") (pinfunction "CTS_18") (pintype "bidirectional"))
    )
    (net (code "61") (name "unconnected-(J2-F0{slash}~{INT}-Pad47)") (class "Default")
      (node (ref "J2") (pin "47") (pinfunction "F0/~{INT}_47") (pintype "bidirectional"))
    )
    (net (code "62") (name "unconnected-(J2-F1{slash}~{CS}-Pad49)") (class "Default")
      (node (ref "J2") (pin "49") (pinfunction "F1/~{CS}_49") (pintype "bidirectional"))
    )
    (net (code "63") (name "unconnected-(J2-F2{slash}PWM-Pad51)") (class "Default")
      (node (ref "J2") (pin "51") (pinfunction "F2/PWM_51") (pintype "bidirectional"))
    )
    (net (code "64") (name "unconnected-(J2-F6-Pad59)") (class "Default")
      (node (ref "J2") (pin "59") (pinfunction "F6_59") (pintype "bidirectional"))
    )
    (net (code "65") (name "unconnected-(J2-F7-Pad61)") (class "Default")
      (node (ref "J2") (pin "61") (pinfunction "F7_61") (pintype "bidirectional"))
    )
    (net (code "66") (name "unconnected-(J2-I2C_~{INT}-Pad23)") (class "Default")
      (node (ref "J2") (pin "23") (pinfunction "I2C_~{INT}_23") (pintype "bidirectional"))
    )
    (net (code "67") (name "unconnected-(J2-RTS-Pad16)") (class "Default")
      (node (ref "J2") (pin "16") (pinfunction "RTS_16") (pintype "bidirectional"))
    )
    (net (code "68") (name "unconnected-(J2-SPI_SCK-Pad3)") (class "Default")
      (node (ref "J2") (pin "3") (pinfunction "SPI_SCK_3") (pintype "bidirectional"))
    )
    (net (code "69") (name "unconnected-(J2-SPI_SDI-Pad5)") (class "Default")
      (node (ref "J2") (pin "5") (pinfunction "SPI_SDI_5") (pintype "bidirectional"))
    )
    (net (code "70") (name "unconnected-(J2-SPI_SDO-Pad7)") (class "Default")
      (node (ref "J2") (pin "7") (pinfunction "SPI_SDO_7") (pintype "bidirectional"))
    )
    (net (code "71") (name "unconnected-(J2-USBHOST_D+-Pad35)") (class "Default")
      (node (ref "J2") (pin "35") (pinfunction "USBHOST_D+_35") (pintype "bidirectional"))
    )
    (net (code "72") (name "unconnected-(J2-USBHOST_D--Pad37)") (class "Default")
      (node (ref "J2") (pin "37") (pinfunction "USBHOST_D-_37") (pintype "bidirectional"))
    )
    (net (code "73") (name "unconnected-(J2-USB_VIN-Pad70)") (class "Default")
      (node (ref "J2") (pin "70") (pinfunction "USB_VIN_70") (pintype "bidirectional"))
    )
    (net (code "74") (name "unconnected-(J5-VPP-PadS5)") (class "Default")
      (node (ref "J5") (pin "S5") (pinfunction "VPP_S5") (pintype "input"))
    )
    (net (code "75") (name "unconnected-(J6-SIM_~{PRESENT}-Pad16)") (class "Default")
      (node (ref "J6") (pin "16") (pinfunction "SIM_~{PRESENT}_16") (pintype "bidirectional"))
    )
    (net (code "76") (name "unconnected-(J6-~{RST}-Pad67)") (class "Default")
      (node (ref "J6") (pin "67") (pinfunction "~{RST}_67") (pintype "bidirectional"))
    )
  )
)
